# current_shunt.net
KiCad netlist of a schematic drawn in EAGLE
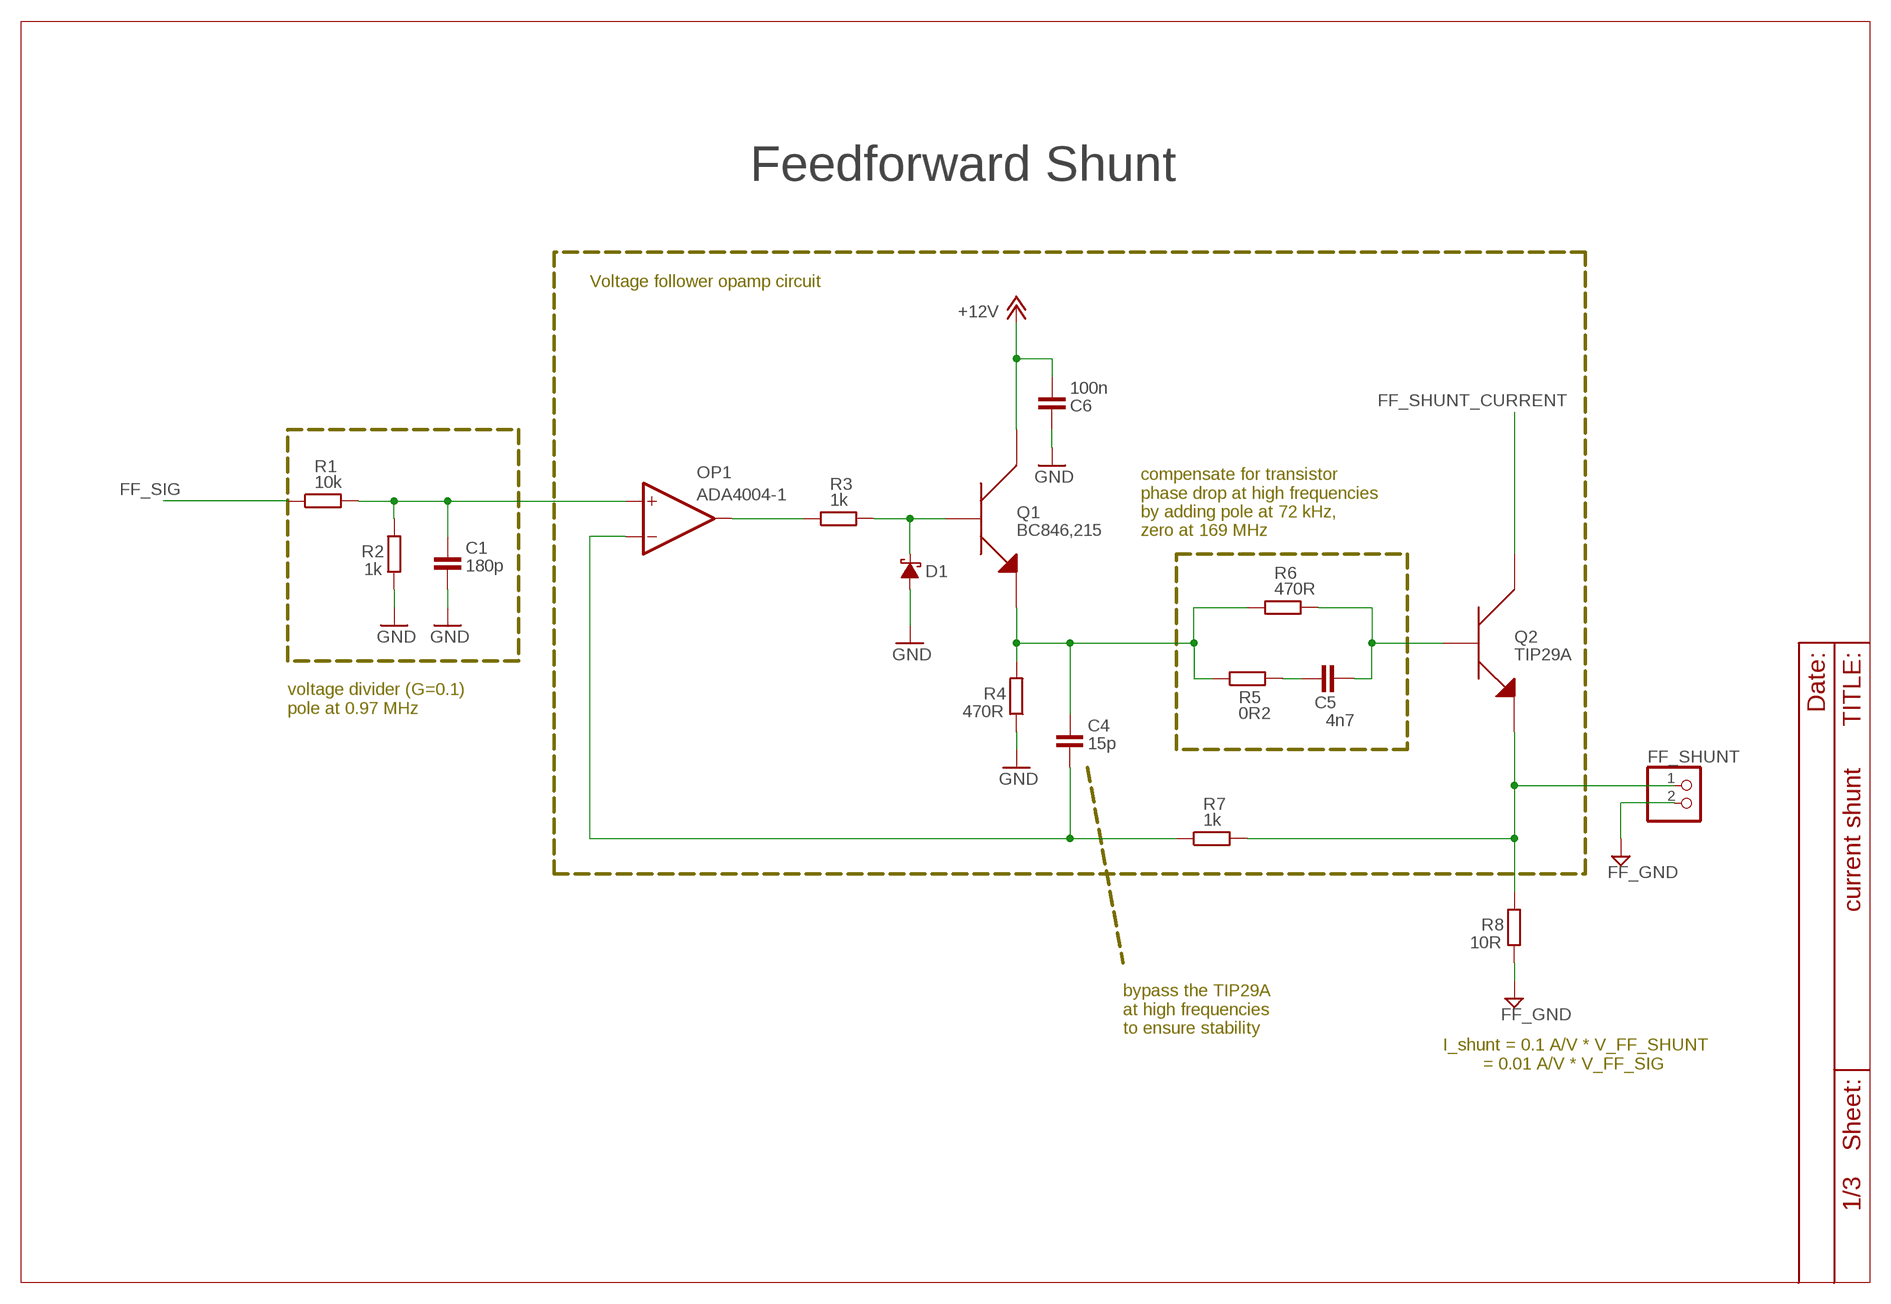
[diagram p0: schematic, sheet 1]
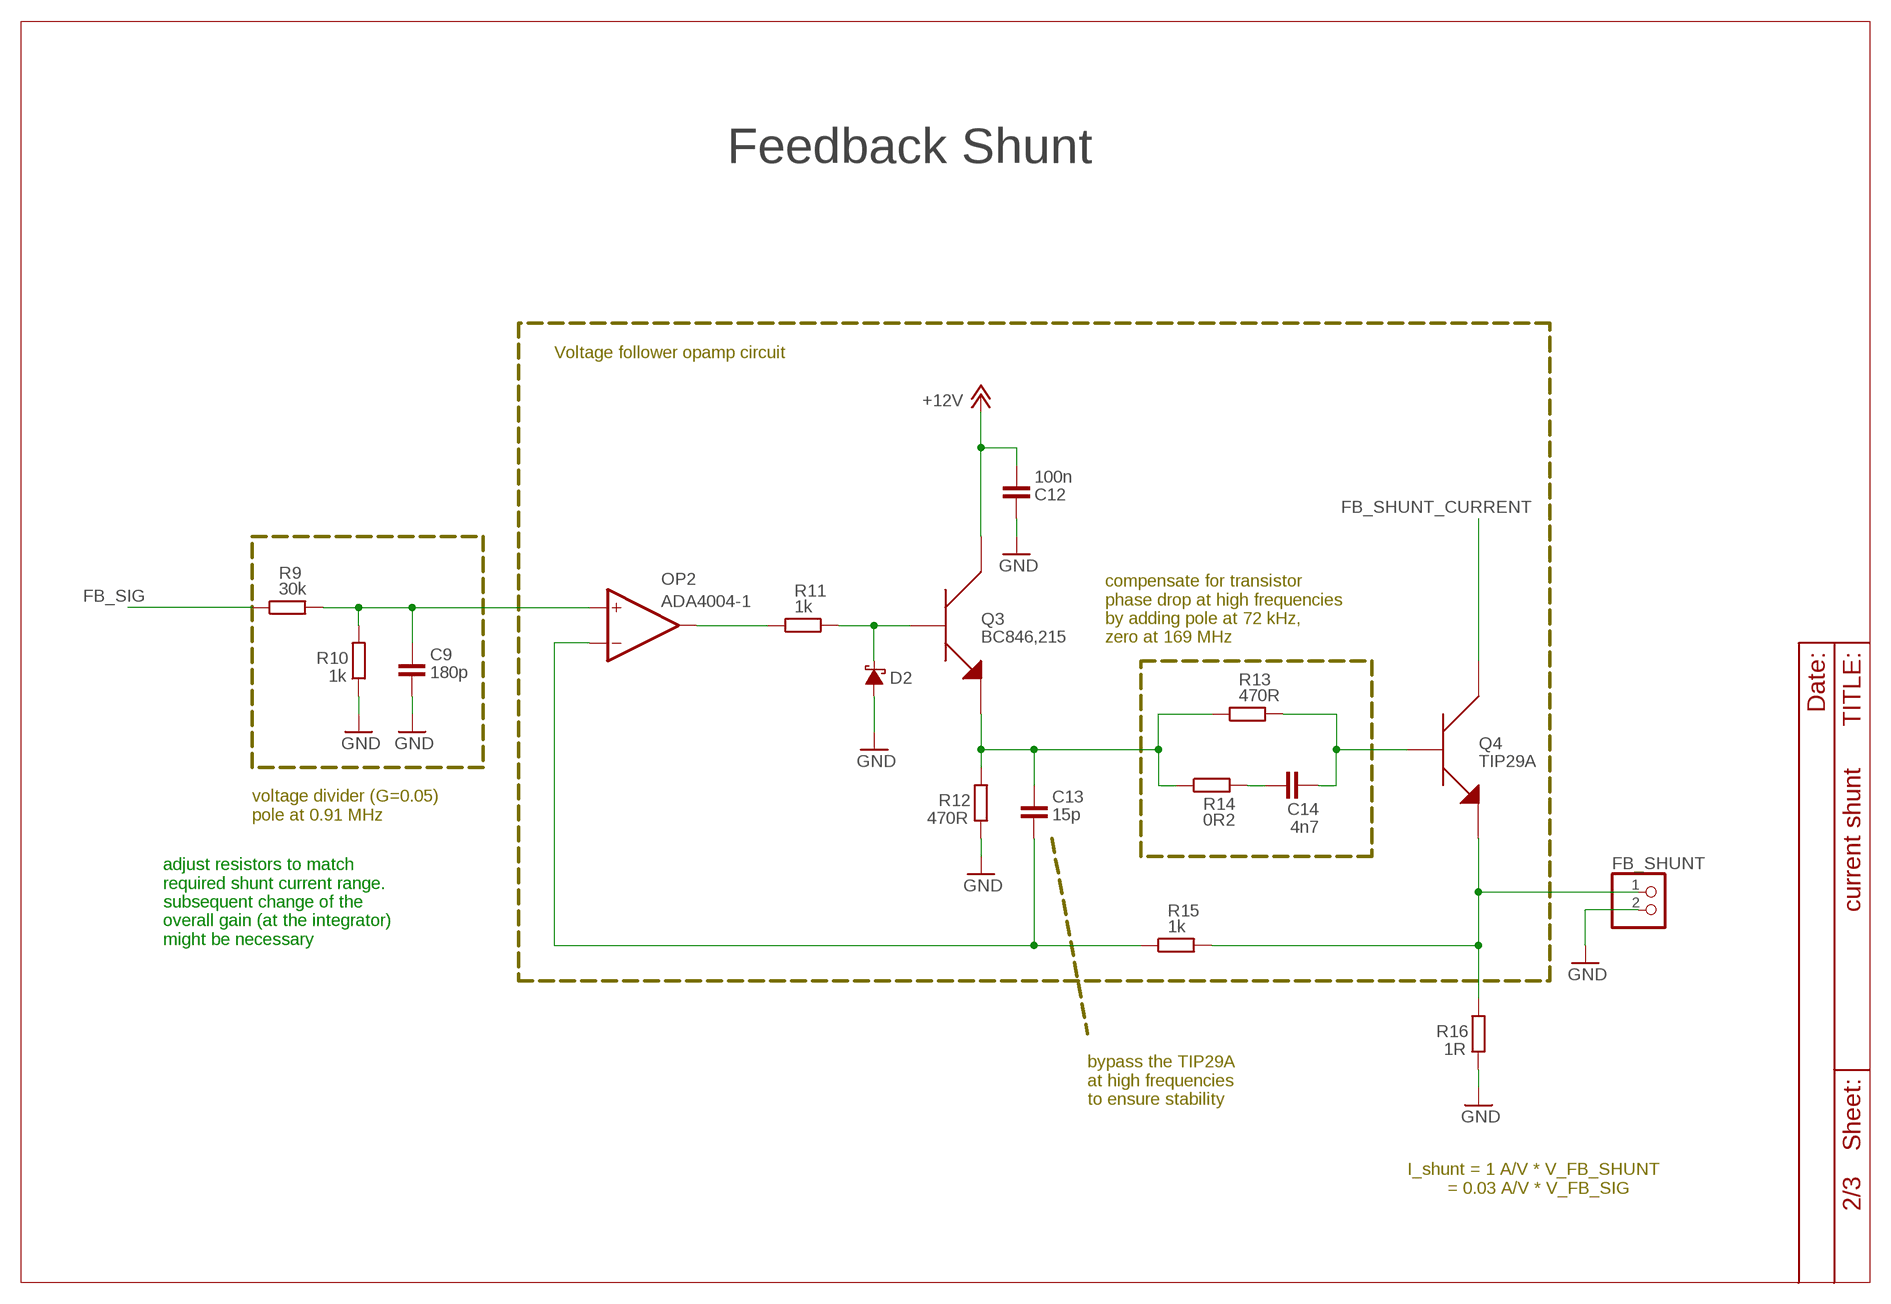
[diagram p1: schematic, sheet 2]
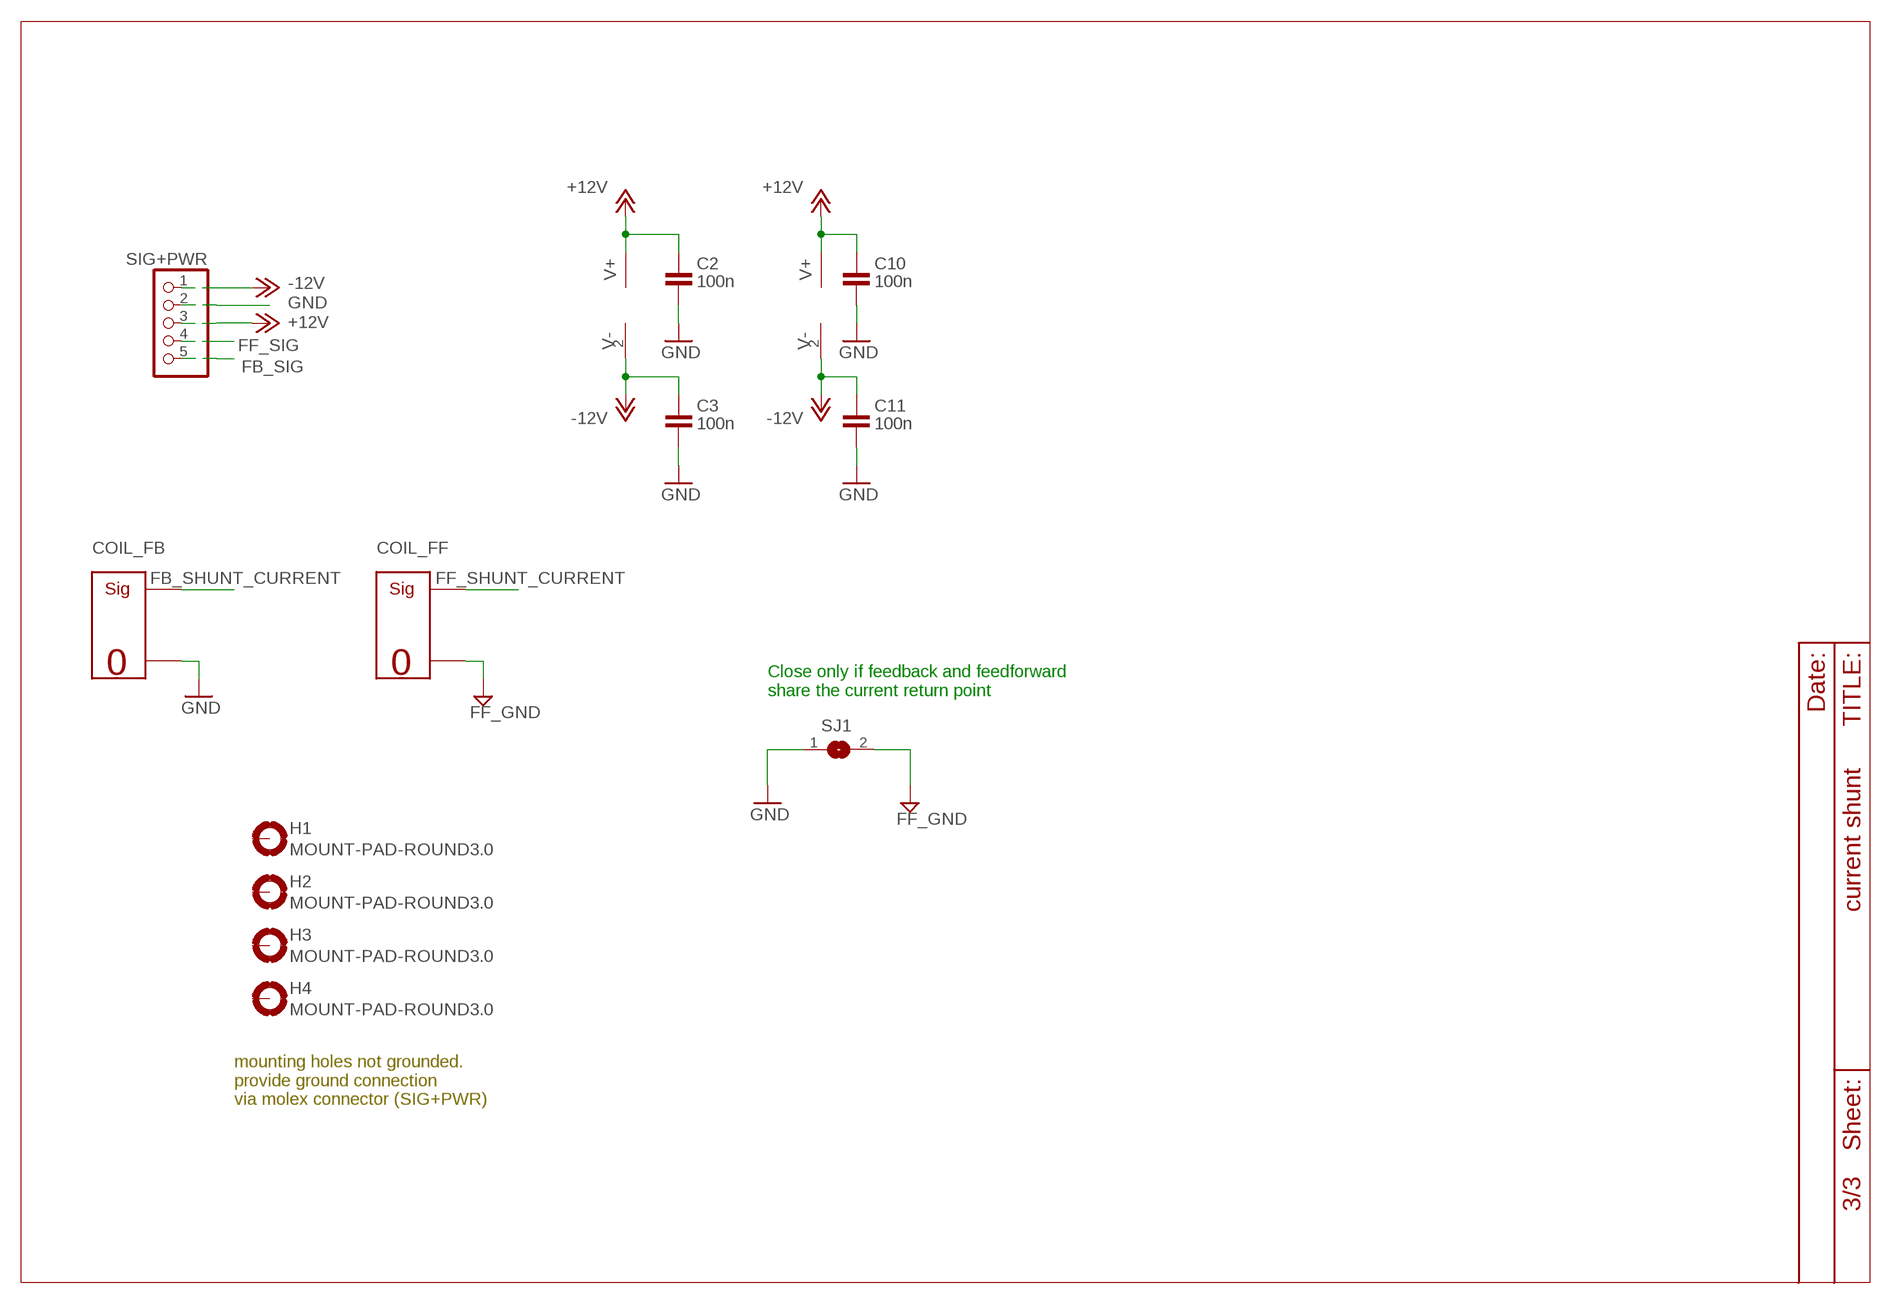
[diagram p2: schematic, sheet 3]

(export (version "E")
  (design (tool "Eeschema 10.0.6"))
  (components
    (comp (ref "C2")
      (value "100n")
      (footprint "eagle-import:0603")
      (libsource (lib "eagle-import") (part "CAP0603"))
    )
    (comp (ref "C3")
      (value "100n")
      (footprint "eagle-import:0603")
      (libsource (lib "eagle-import") (part "CAP0603"))
    )
    (comp (ref "C10")
      (value "100n")
      (footprint "eagle-import:0603")
      (libsource (lib "eagle-import") (part "CAP0603"))
    )
    (comp (ref "C11")
      (value "100n")
      (footprint "eagle-import:0603")
      (libsource (lib "eagle-import") (part "CAP0603"))
    )
    (comp (ref "COIL_FB")
      (value "MOLEX_SIG_2PIN")
      (footprint "eagle-import:MOLEX-2PIN")
      (libsource (lib "eagle-import") (part "MOLEX_SIG_2PIN"))
    )
    (comp (ref "COIL_FF")
      (value "MOLEX_SIG_2PIN")
      (footprint "eagle-import:MOLEX-2PIN")
      (libsource (lib "eagle-import") (part "MOLEX_SIG_2PIN"))
    )
    (comp (ref "H1")
      (value "MOUNT-PAD-ROUND3.0")
      (footprint "eagle-import:3,0-PAD")
      (libsource (lib "eagle-import") (part "MOUNT-PAD-ROUND3.0"))
    )
    (comp (ref "H2")
      (value "MOUNT-PAD-ROUND3.0")
      (footprint "eagle-import:3,0-PAD")
      (libsource (lib "eagle-import") (part "MOUNT-PAD-ROUND3.0"))
    )
    (comp (ref "H3")
      (value "MOUNT-PAD-ROUND3.0")
      (footprint "eagle-import:3,0-PAD")
      (libsource (lib "eagle-import") (part "MOUNT-PAD-ROUND3.0"))
    )
    (comp (ref "H4")
      (value "MOUNT-PAD-ROUND3.0")
      (footprint "eagle-import:3,0-PAD")
      (libsource (lib "eagle-import") (part "MOUNT-PAD-ROUND3.0"))
    )
    (comp (ref "OP1")
      (value "ADA4004-1")
      (footprint "eagle-import:SOT23-5")
      (libsource (lib "eagle-import") (part "OPAMPSOT23-5"))
    )
    (comp (ref "OP2")
      (value "ADA4004-1")
      (footprint "eagle-import:SOT23-5")
      (libsource (lib "eagle-import") (part "OPAMPSOT23-5"))
    )
    (comp (ref "SIG+PWR")
      (value "MOLEX-KK-1X5")
      (footprint "eagle-import:MOLEX-KK-5PIN")
      (libsource (lib "eagle-import") (part "MOLEX-KK-1X5"))
    )
    (comp (ref "SJ1") (value "SJ") (footprint "eagle-import:SJ") (libsource (lib "eagle-import") (part "SJ")))
    (comp (ref "C1")
      (value "180p")
      (footprint "eagle-import:0603")
      (libsource (lib "eagle-import") (part "CAP0603"))
    )
    (comp (ref "C4")
      (value "15p")
      (footprint "eagle-import:0603")
      (libsource (lib "eagle-import") (part "CAP0603"))
    )
    (comp (ref "C5")
      (value "4n7")
      (footprint "eagle-import:0603")
      (libsource (lib "eagle-import") (part "CAP0603"))
    )
    (comp (ref "C6")
      (value "100n")
      (footprint "eagle-import:0603")
      (libsource (lib "eagle-import") (part "CAP0603"))
    )
    (comp (ref "D1")
      (value "DIODE_SCHOTTKY")
      (footprint "eagle-import:SOD123F")
      (libsource (lib "eagle-import") (part "DIODE_SCHOTTKY"))
    )
    (comp (ref "FF_SHUNT")
      (value "PINHD-1X2")
      (footprint "eagle-import:1X02")
      (libsource (lib "eagle-import") (part "PINHD-1X2"))
    )
    (comp (ref "Q1")
      (value "BC846,215")
      (footprint "eagle-import:SOT23")
      (libsource (lib "eagle-import") (part "BC846,215"))
    )
    (comp (ref "Q2")
      (value "TIP29A")
      (footprint "eagle-import:TO-220_DETATCHED")
      (libsource (lib "eagle-import") (part "TIP29A"))
    )
    (comp (ref "R1")
      (value "10k")
      (footprint "eagle-import:0603")
      (libsource (lib "eagle-import") (part "RES0603"))
    )
    (comp (ref "R2")
      (value "1k")
      (footprint "eagle-import:0603")
      (libsource (lib "eagle-import") (part "RES0603"))
    )
    (comp (ref "R3")
      (value "1k")
      (footprint "eagle-import:0603")
      (libsource (lib "eagle-import") (part "RES0603"))
    )
    (comp (ref "R4")
      (value "470R")
      (footprint "eagle-import:0603")
      (libsource (lib "eagle-import") (part "RES0603"))
    )
    (comp (ref "R5")
      (value "0R2")
      (footprint "eagle-import:0603")
      (libsource (lib "eagle-import") (part "RES0603"))
    )
    (comp (ref "R6")
      (value "470R")
      (footprint "eagle-import:0603")
      (libsource (lib "eagle-import") (part "RES0603"))
    )
    (comp (ref "R7")
      (value "1k")
      (footprint "eagle-import:0603")
      (libsource (lib "eagle-import") (part "RES0603"))
    )
    (comp (ref "R8")
      (value "10R")
      (footprint "eagle-import:0603")
      (libsource (lib "eagle-import") (part "RES0603"))
    )
    (comp (ref "C9")
      (value "180p")
      (footprint "eagle-import:0603")
      (libsource (lib "eagle-import") (part "CAP0603"))
    )
    (comp (ref "C12")
      (value "100n")
      (footprint "eagle-import:0603")
      (libsource (lib "eagle-import") (part "CAP0603"))
    )
    (comp (ref "C13")
      (value "15p")
      (footprint "eagle-import:0603")
      (libsource (lib "eagle-import") (part "CAP0603"))
    )
    (comp (ref "C14")
      (value "4n7")
      (footprint "eagle-import:0603")
      (libsource (lib "eagle-import") (part "CAP0603"))
    )
    (comp (ref "D2")
      (value "DIODE_SCHOTTKY")
      (footprint "eagle-import:SOD123F")
      (libsource (lib "eagle-import") (part "DIODE_SCHOTTKY"))
    )
    (comp (ref "FB_SHUNT")
      (value "PINHD-1X2")
      (footprint "eagle-import:1X02")
      (libsource (lib "eagle-import") (part "PINHD-1X2"))
    )
    (comp (ref "Q3")
      (value "BC846,215")
      (footprint "eagle-import:SOT23")
      (libsource (lib "eagle-import") (part "BC846,215"))
    )
    (comp (ref "Q4")
      (value "TIP29A")
      (footprint "eagle-import:TO-220_DETATCHED")
      (libsource (lib "eagle-import") (part "TIP29A"))
    )
    (comp (ref "R9")
      (value "30k")
      (footprint "eagle-import:0603")
      (libsource (lib "eagle-import") (part "RES0603"))
    )
    (comp (ref "R10")
      (value "1k")
      (footprint "eagle-import:0603")
      (libsource (lib "eagle-import") (part "RES0603"))
    )
    (comp (ref "R11")
      (value "1k")
      (footprint "eagle-import:0603")
      (libsource (lib "eagle-import") (part "RES0603"))
    )
    (comp (ref "R12")
      (value "470R")
      (footprint "eagle-import:0603")
      (libsource (lib "eagle-import") (part "RES0603"))
    )
    (comp (ref "R13")
      (value "470R")
      (footprint "eagle-import:0603")
      (libsource (lib "eagle-import") (part "RES0603"))
    )
    (comp (ref "R14")
      (value "0R2")
      (footprint "eagle-import:0603")
      (libsource (lib "eagle-import") (part "RES0603"))
    )
    (comp (ref "R15")
      (value "1k")
      (footprint "eagle-import:0603")
      (libsource (lib "eagle-import") (part "RES0603"))
    )
    (comp (ref "R16")
      (value "1R")
      (footprint "eagle-import:0603")
      (libsource (lib "eagle-import") (part "RES0603"))
    )
  )
  (nets
    (net (code "1") (name "+12V") (class "Default")
      (node (ref "C10") (pin "1") (pinfunction "1_1") (pintype "passive"))
      (node (ref "C12") (pin "1") (pinfunction "1_1") (pintype "passive"))
      (node (ref "C2") (pin "1") (pinfunction "1_1") (pintype "passive"))
      (node (ref "C6") (pin "1") (pinfunction "1_1") (pintype "passive"))
      (node (ref "OP1") (pin "5") (pinfunction "V+_5") (pintype "power_in"))
      (node (ref "OP2") (pin "5") (pinfunction "V+_5") (pintype "power_in"))
      (node (ref "Q1") (pin "3") (pinfunction "COLLECTOR_3") (pintype "bidirectional"))
      (node (ref "Q3") (pin "3") (pinfunction "COLLECTOR_3") (pintype "bidirectional"))
      (node (ref "SIG+PWR") (pin "3") (pinfunction "3_3") (pintype "passive"))
    )
    (net (code "2") (name "-12V") (class "Default")
      (node (ref "C11") (pin "1") (pinfunction "1_1") (pintype "passive"))
      (node (ref "C3") (pin "1") (pinfunction "1_1") (pintype "passive"))
      (node (ref "OP1") (pin "2") (pinfunction "V-_2") (pintype "power_in"))
      (node (ref "OP2") (pin "2") (pinfunction "V-_2") (pintype "power_in"))
      (node (ref "SIG+PWR") (pin "1") (pinfunction "1_1") (pintype "passive"))
    )
    (net (code "3") (name "FB_SHUNT_CURRENT") (class "Default")
      (node (ref "COIL_FB") (pin "2") (pinfunction "SIG_2") (pintype "bidirectional"))
      (node (ref "Q4") (pin "COLLECTOR") (pinfunction "COLLECTOR_COLLECTOR") (pintype "bidirectional"))
    )
    (net (code "4") (name "FB_SIG") (class "Default")
      (node (ref "R9") (pin "1") (pinfunction "1_1") (pintype "passive"))
      (node (ref "SIG+PWR") (pin "5") (pinfunction "5_5") (pintype "passive"))
    )
    (net (code "5") (name "FF_GND") (class "Default")
      (node (ref "COIL_FF") (pin "1") (pinfunction "GND_1") (pintype "power_in"))
      (node (ref "FF_SHUNT") (pin "2") (pinfunction "2_2") (pintype "passive"))
      (node (ref "R8") (pin "1") (pinfunction "1_1") (pintype "passive"))
      (node (ref "SJ1") (pin "2") (pinfunction "2_2") (pintype "passive"))
    )
    (net (code "6") (name "FF_SHUNT_CURRENT") (class "Default")
      (node (ref "COIL_FF") (pin "2") (pinfunction "SIG_2") (pintype "bidirectional"))
      (node (ref "Q2") (pin "COLLECTOR") (pinfunction "COLLECTOR_COLLECTOR") (pintype "bidirectional"))
    )
    (net (code "7") (name "FF_SIG") (class "Default")
      (node (ref "R1") (pin "1") (pinfunction "1_1") (pintype "passive"))
      (node (ref "SIG+PWR") (pin "4") (pinfunction "4_4") (pintype "passive"))
    )
    (net (code "8") (name "GND") (class "Default")
      (node (ref "C1") (pin "2") (pinfunction "2_2") (pintype "passive"))
      (node (ref "C10") (pin "2") (pinfunction "2_2") (pintype "passive"))
      (node (ref "C11") (pin "2") (pinfunction "2_2") (pintype "passive"))
      (node (ref "C12") (pin "2") (pinfunction "2_2") (pintype "passive"))
      (node (ref "C2") (pin "2") (pinfunction "2_2") (pintype "passive"))
      (node (ref "C3") (pin "2") (pinfunction "2_2") (pintype "passive"))
      (node (ref "C6") (pin "2") (pinfunction "2_2") (pintype "passive"))
      (node (ref "C9") (pin "2") (pinfunction "2_2") (pintype "passive"))
      (node (ref "COIL_FB") (pin "1") (pinfunction "GND_1") (pintype "power_in"))
      (node (ref "D1") (pin "P$2") (pinfunction "A_P$2") (pintype "passive"))
      (node (ref "D2") (pin "P$2") (pinfunction "A_P$2") (pintype "passive"))
      (node (ref "FB_SHUNT") (pin "2") (pinfunction "2_2") (pintype "passive"))
      (node (ref "R10") (pin "1") (pinfunction "1_1") (pintype "passive"))
      (node (ref "R12") (pin "1") (pinfunction "1_1") (pintype "passive"))
      (node (ref "R16") (pin "1") (pinfunction "1_1") (pintype "passive"))
      (node (ref "R2") (pin "1") (pinfunction "1_1") (pintype "passive"))
      (node (ref "R4") (pin "1") (pinfunction "1_1") (pintype "passive"))
      (node (ref "SIG+PWR") (pin "2") (pinfunction "2_2") (pintype "passive"))
      (node (ref "SJ1") (pin "1") (pinfunction "1_1") (pintype "passive"))
    )
    (net (code "9") (name "Net-(C5-Pad1)") (class "Default")
      (node (ref "C5") (pin "1") (pinfunction "1_1") (pintype "passive"))
      (node (ref "R5") (pin "2") (pinfunction "2_2") (pintype "passive"))
    )
    (net (code "10") (name "Net-(C5-Pad2)") (class "Default")
      (node (ref "C5") (pin "2") (pinfunction "2_2") (pintype "passive"))
      (node (ref "Q2") (pin "BASE") (pinfunction "BASE_BASE") (pintype "bidirectional"))
      (node (ref "R6") (pin "2") (pinfunction "2_2") (pintype "passive"))
    )
    (net (code "11") (name "Net-(C14-Pad1)") (class "Default")
      (node (ref "C14") (pin "1") (pinfunction "1_1") (pintype "passive"))
      (node (ref "R14") (pin "2") (pinfunction "2_2") (pintype "passive"))
    )
    (net (code "12") (name "Net-(C14-Pad2)") (class "Default")
      (node (ref "C14") (pin "2") (pinfunction "2_2") (pintype "passive"))
      (node (ref "Q4") (pin "BASE") (pinfunction "BASE_BASE") (pintype "bidirectional"))
      (node (ref "R13") (pin "2") (pinfunction "2_2") (pintype "passive"))
    )
    (net (code "13") (name "Net-(D1-K)") (class "Default")
      (node (ref "D1") (pin "P$1") (pinfunction "K_P$1") (pintype "passive"))
      (node (ref "Q1") (pin "1") (pinfunction "BASE_1") (pintype "bidirectional"))
      (node (ref "R3") (pin "2") (pinfunction "2_2") (pintype "passive"))
    )
    (net (code "14") (name "Net-(D2-K)") (class "Default")
      (node (ref "D2") (pin "P$1") (pinfunction "K_P$1") (pintype "passive"))
      (node (ref "Q3") (pin "1") (pinfunction "BASE_1") (pintype "bidirectional"))
      (node (ref "R11") (pin "2") (pinfunction "2_2") (pintype "passive"))
    )
    (net (code "15") (name "Net-(FB_SHUNT-Pad1)") (class "Default")
      (node (ref "FB_SHUNT") (pin "1") (pinfunction "1_1") (pintype "passive"))
      (node (ref "Q4") (pin "EMITTER") (pinfunction "EMITTER_EMITTER") (pintype "bidirectional"))
      (node (ref "R15") (pin "2") (pinfunction "2_2") (pintype "passive"))
      (node (ref "R16") (pin "2") (pinfunction "2_2") (pintype "passive"))
    )
    (net (code "16") (name "Net-(FF_SHUNT-Pad1)") (class "Default")
      (node (ref "FF_SHUNT") (pin "1") (pinfunction "1_1") (pintype "passive"))
      (node (ref "Q2") (pin "EMITTER") (pinfunction "EMITTER_EMITTER") (pintype "bidirectional"))
      (node (ref "R7") (pin "2") (pinfunction "2_2") (pintype "passive"))
      (node (ref "R8") (pin "2") (pinfunction "2_2") (pintype "passive"))
    )
    (net (code "17") (name "Net-(OP1A-+IN)") (class "Default")
      (node (ref "C1") (pin "1") (pinfunction "1_1") (pintype "passive"))
      (node (ref "OP1") (pin "3") (pinfunction "+IN_3") (pintype "input"))
      (node (ref "R1") (pin "2") (pinfunction "2_2") (pintype "passive"))
      (node (ref "R2") (pin "2") (pinfunction "2_2") (pintype "passive"))
    )
    (net (code "18") (name "Net-(OP1A--IN)") (class "Default")
      (node (ref "C4") (pin "2") (pinfunction "2_2") (pintype "passive"))
      (node (ref "OP1") (pin "4") (pinfunction "-IN_4") (pintype "input"))
      (node (ref "R7") (pin "1") (pinfunction "1_1") (pintype "passive"))
    )
    (net (code "19") (name "Net-(OP1A-OUT)") (class "Default")
      (node (ref "OP1") (pin "1") (pinfunction "OUT_1") (pintype "output"))
      (node (ref "R3") (pin "1") (pinfunction "1_1") (pintype "passive"))
    )
    (net (code "20") (name "Net-(OP2A-+IN)") (class "Default")
      (node (ref "C9") (pin "1") (pinfunction "1_1") (pintype "passive"))
      (node (ref "OP2") (pin "3") (pinfunction "+IN_3") (pintype "input"))
      (node (ref "R10") (pin "2") (pinfunction "2_2") (pintype "passive"))
      (node (ref "R9") (pin "2") (pinfunction "2_2") (pintype "passive"))
    )
    (net (code "21") (name "Net-(OP2A--IN)") (class "Default")
      (node (ref "C13") (pin "2") (pinfunction "2_2") (pintype "passive"))
      (node (ref "OP2") (pin "4") (pinfunction "-IN_4") (pintype "input"))
      (node (ref "R15") (pin "1") (pinfunction "1_1") (pintype "passive"))
    )
    (net (code "22") (name "Net-(OP2A-OUT)") (class "Default")
      (node (ref "OP2") (pin "1") (pinfunction "OUT_1") (pintype "output"))
      (node (ref "R11") (pin "1") (pinfunction "1_1") (pintype "passive"))
    )
    (net (code "23") (name "Net-(Q1-EMITTER)") (class "Default")
      (node (ref "C4") (pin "1") (pinfunction "1_1") (pintype "passive"))
      (node (ref "Q1") (pin "2") (pinfunction "EMITTER_2") (pintype "bidirectional"))
      (node (ref "R4") (pin "2") (pinfunction "2_2") (pintype "passive"))
      (node (ref "R5") (pin "1") (pinfunction "1_1") (pintype "passive"))
      (node (ref "R6") (pin "1") (pinfunction "1_1") (pintype "passive"))
    )
    (net (code "24") (name "Net-(Q3-EMITTER)") (class "Default")
      (node (ref "C13") (pin "1") (pinfunction "1_1") (pintype "passive"))
      (node (ref "Q3") (pin "2") (pinfunction "EMITTER_2") (pintype "bidirectional"))
      (node (ref "R12") (pin "2") (pinfunction "2_2") (pintype "passive"))
      (node (ref "R13") (pin "1") (pinfunction "1_1") (pintype "passive"))
      (node (ref "R14") (pin "1") (pinfunction "1_1") (pintype "passive"))
    )
    (net (code "25") (name "unconnected-(H1-MOUNT-PadB3,0)") (class "Default")
      (node (ref "H1") (pin "B3,0") (pinfunction "MOUNT_B3,0") (pintype "passive"))
    )
    (net (code "26") (name "unconnected-(H2-MOUNT-PadB3,0)") (class "Default")
      (node (ref "H2") (pin "B3,0") (pinfunction "MOUNT_B3,0") (pintype "passive"))
    )
    (net (code "27") (name "unconnected-(H3-MOUNT-PadB3,0)") (class "Default")
      (node (ref "H3") (pin "B3,0") (pinfunction "MOUNT_B3,0") (pintype "passive"))
    )
    (net (code "28") (name "unconnected-(H4-MOUNT-PadB3,0)") (class "Default")
      (node (ref "H4") (pin "B3,0") (pinfunction "MOUNT_B3,0") (pintype "passive"))
    )
  )
)
